# simple-loop-active3.net
KiCad netlist of a schematic drawn in EAGLE
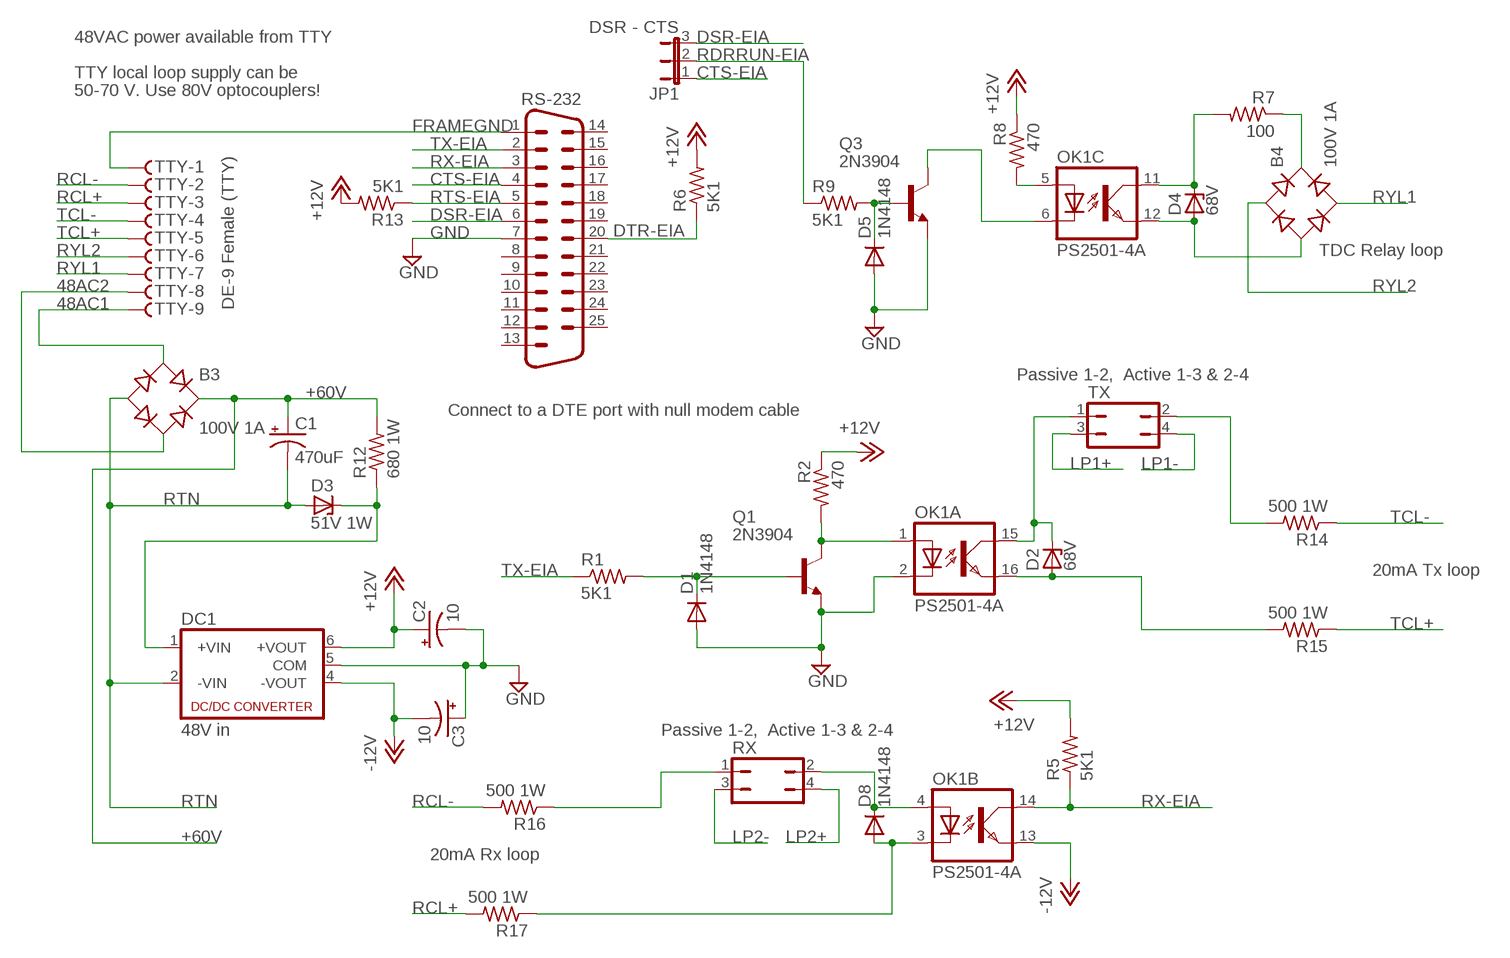
[diagram p0: schematic, sheet 1]
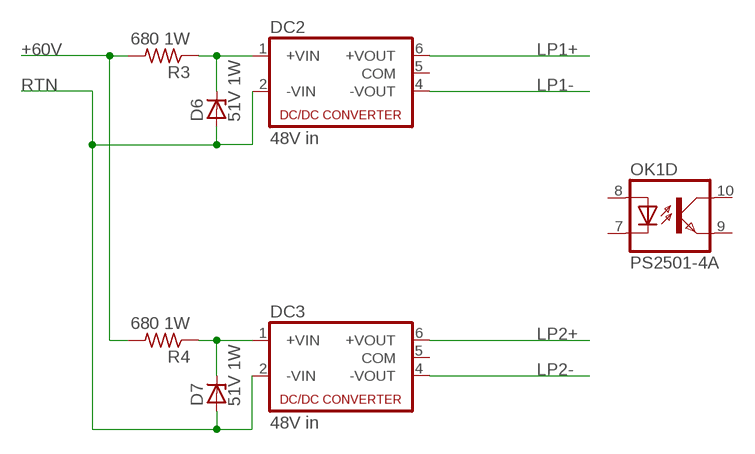
[diagram p1: schematic, sheet 2]

(export (version "E")
  (design (tool "Eeschema 10.0.6"))
  (components
    (comp (ref "D6")
      (value "51V 1W")
      (footprint "eagle-import:DO41Z10")
      (libsource (lib "eagle-import") (part "ZENER-DIODEDO41Z10"))
    )
    (comp (ref "D7")
      (value "51V 1W")
      (footprint "eagle-import:DO41Z10")
      (libsource (lib "eagle-import") (part "ZENER-DIODEDO41Z10"))
    )
    (comp (ref "DC2")
      (value "48V in")
      (footprint "eagle-import:NMA")
      (fields (field (name "MF") "C & D TECHNOLOGIES, INC") (field (name "MPN") "NMA0515SC"))
      (libsource (lib "eagle-import") (part "NMA"))
    )
    (comp (ref "DC3")
      (value "48V in")
      (footprint "eagle-import:NMA")
      (fields (field (name "MF") "C & D TECHNOLOGIES, INC") (field (name "MPN") "NMA0515SC"))
      (libsource (lib "eagle-import") (part "NMA"))
    )
    (comp (ref "OK1")
      (value "PS2501-4A")
      (footprint "eagle-import:DIL16")
      (fields (field (name "MF") "VISHAY/TELEFUNKEN") (field (name "MPN") "ILQ1"))
      (libsource (lib "eagle-import") (part "ILQ1"))
    )
    (comp (ref "R3")
      (value "680 1W")
      (footprint "eagle-import:P0817V")
      (libsource (lib "eagle-import") (part "R-US_0817/7V"))
    )
    (comp (ref "R4")
      (value "680 1W")
      (footprint "eagle-import:P0817V")
      (libsource (lib "eagle-import") (part "R-US_0817/7V"))
    )
    (comp (ref "B3")
      (value "100V 1A")
      (footprint "eagle-import:RB1A")
      (libsource (lib "eagle-import") (part "RB1A"))
    )
    (comp (ref "B4")
      (value "100V 1A")
      (footprint "eagle-import:RB1A")
      (libsource (lib "eagle-import") (part "RB1A"))
    )
    (comp (ref "C1")
      (value "470uF")
      (footprint "eagle-import:E7,5-18")
      (libsource (lib "eagle-import") (part "CPOL-USE7.5-18"))
    )
    (comp (ref "C2")
      (value "10")
      (footprint "eagle-import:B45181A")
      (libsource (lib "eagle-import") (part "CPOL-USB45181A"))
    )
    (comp (ref "C3")
      (value "10")
      (footprint "eagle-import:B45181A")
      (libsource (lib "eagle-import") (part "CPOL-USB45181A"))
    )
    (comp (ref "D1")
      (value "1N4148")
      (footprint "eagle-import:DO35-10")
      (libsource (lib "eagle-import") (part "1N4148DO35-10"))
    )
    (comp (ref "D2")
      (value "68V")
      (footprint "eagle-import:DO41Z10")
      (libsource (lib "eagle-import") (part "ZENER-DIODEDO41Z10"))
    )
    (comp (ref "D3")
      (value "51V 1W")
      (footprint "eagle-import:DO41Z10")
      (libsource (lib "eagle-import") (part "ZENER-DIODEDO41Z10"))
    )
    (comp (ref "D4")
      (value "68V")
      (footprint "eagle-import:DO41Z10")
      (libsource (lib "eagle-import") (part "ZENER-DIODEDO41Z10"))
    )
    (comp (ref "D5")
      (value "1N4148")
      (footprint "eagle-import:DO35-10")
      (libsource (lib "eagle-import") (part "1N4148DO35-10"))
    )
    (comp (ref "D8")
      (value "1N4148")
      (footprint "eagle-import:DO35-10")
      (libsource (lib "eagle-import") (part "1N4148DO35-10"))
    )
    (comp (ref "DC1")
      (value "48V in")
      (footprint "eagle-import:NMA")
      (fields (field (name "MF") "C & D TECHNOLOGIES, INC") (field (name "MPN") "NMA0515SC"))
      (libsource (lib "eagle-import") (part "NMA"))
    )
    (comp (ref "JP1")
      (value "DSR - CTS")
      (footprint "eagle-import:JP2")
      (libsource (lib "eagle-import") (part "JP2E"))
    )
    (comp (ref "Q1")
      (value "2N3904")
      (footprint "eagle-import:TO92")
      (libsource (lib "eagle-import") (part "2N3904"))
    )
    (comp (ref "Q3")
      (value "2N3904")
      (footprint "eagle-import:TO92")
      (libsource (lib "eagle-import") (part "2N3904"))
    )
    (comp (ref "R1")
      (value "5K1")
      (footprint "eagle-import:0207_10")
      (libsource (lib "eagle-import") (part "R-US_0207/10"))
    )
    (comp (ref "R2")
      (value "470")
      (footprint "eagle-import:0207_10")
      (libsource (lib "eagle-import") (part "R-US_0207/10"))
    )
    (comp (ref "R5")
      (value "5K1")
      (footprint "eagle-import:0207_10")
      (libsource (lib "eagle-import") (part "R-US_0207/10"))
    )
    (comp (ref "R6")
      (value "5K1")
      (footprint "eagle-import:0207_10")
      (libsource (lib "eagle-import") (part "R-US_0207/10"))
    )
    (comp (ref "R7")
      (value "100")
      (footprint "eagle-import:0207_10")
      (libsource (lib "eagle-import") (part "R-US_0207/10"))
    )
    (comp (ref "R8")
      (value "470")
      (footprint "eagle-import:0207_10")
      (libsource (lib "eagle-import") (part "R-US_0207/10"))
    )
    (comp (ref "R9")
      (value "5K1")
      (footprint "eagle-import:0207_10")
      (libsource (lib "eagle-import") (part "R-US_0207/10"))
    )
    (comp (ref "R12")
      (value "680 1W")
      (footprint "eagle-import:P0817V")
      (libsource (lib "eagle-import") (part "R-US_0817/7V"))
    )
    (comp (ref "R13")
      (value "5K1")
      (footprint "eagle-import:0207_10")
      (libsource (lib "eagle-import") (part "R-US_0207/10"))
    )
    (comp (ref "R14")
      (value "500 1W")
      (footprint "eagle-import:P0817V")
      (libsource (lib "eagle-import") (part "R-US_0817/7V"))
    )
    (comp (ref "R15")
      (value "500 1W")
      (footprint "eagle-import:P0817V")
      (libsource (lib "eagle-import") (part "R-US_0817/7V"))
    )
    (comp (ref "R16")
      (value "500 1W")
      (footprint "eagle-import:P0817V")
      (libsource (lib "eagle-import") (part "R-US_0817/7V"))
    )
    (comp (ref "R17")
      (value "500 1W")
      (footprint "eagle-import:P0817V")
      (libsource (lib "eagle-import") (part "R-US_0817/7V"))
    )
    (comp (ref "RS-232")
      (value "M25H")
      (footprint "eagle-import:M25H")
      (libsource (lib "eagle-import") (part "M25H"))
    )
    (comp (ref "RX")
      (value "JP2Q")
      (footprint "eagle-import:JP2Q")
      (libsource (lib "eagle-import") (part "JP2Q"))
    )
    (comp (ref "TTY")
      (value "F09HS")
      (footprint "eagle-import:F09H")
      (libsource (lib "eagle-import") (part "F09?SH"))
    )
    (comp (ref "TX")
      (value "JP2Q")
      (footprint "eagle-import:JP2Q")
      (libsource (lib "eagle-import") (part "JP2Q"))
    )
  )
  (nets
    (net (code "1") (name "+12V") (class "Default")
      (node (ref "C2") (pin "+") (pinfunction "+_+") (pintype "passive"))
      (node (ref "DC1") (pin "6") (pinfunction "+VOUT_6") (pintype "passive"))
      (node (ref "R13") (pin "2") (pinfunction "2_2") (pintype "passive"))
      (node (ref "R2") (pin "1") (pinfunction "1_1") (pintype "passive"))
      (node (ref "R5") (pin "2") (pinfunction "2_2") (pintype "passive"))
      (node (ref "R6") (pin "2") (pinfunction "2_2") (pintype "passive"))
      (node (ref "R8") (pin "1") (pinfunction "1_1") (pintype "passive"))
    )
    (net (code "2") (name "+60V") (class "Default")
      (node (ref "B3") (pin "+") (pinfunction "+_+") (pintype "passive"))
      (node (ref "C1") (pin "+") (pinfunction "+_+") (pintype "passive"))
      (node (ref "R12") (pin "2") (pinfunction "2_2") (pintype "passive"))
      (node (ref "R3") (pin "2") (pinfunction "2_2") (pintype "passive"))
      (node (ref "R4") (pin "2") (pinfunction "2_2") (pintype "passive"))
    )
    (net (code "3") (name "-12V") (class "Default")
      (node (ref "C3") (pin "-") (pinfunction "-_-") (pintype "passive"))
      (node (ref "DC1") (pin "4") (pinfunction "-VOUT_4") (pintype "passive"))
      (node (ref "OK1") (pin "13") (pinfunction "EMIT_13") (pintype "passive"))
    )
    (net (code "4") (name "48AC1") (class "Default")
      (node (ref "B3") (pin "AC1") (pinfunction "AC1_AC1") (pintype "passive"))
      (node (ref "TTY") (pin "9") (pinfunction "F_9") (pintype "passive"))
    )
    (net (code "5") (name "48AC2") (class "Default")
      (node (ref "B3") (pin "AC2") (pinfunction "AC2_AC2") (pintype "passive"))
      (node (ref "TTY") (pin "8") (pinfunction "F_8") (pintype "passive"))
    )
    (net (code "6") (name "CTS-EIA") (class "Default")
      (node (ref "JP1") (pin "1") (pinfunction "1_1") (pintype "passive"))
      (node (ref "RS-232") (pin "4") (pinfunction "4_4") (pintype "passive"))
    )
    (net (code "7") (name "DSR-EIA") (class "Default")
      (node (ref "JP1") (pin "3") (pinfunction "3_3") (pintype "passive"))
      (node (ref "RS-232") (pin "6") (pinfunction "6_6") (pintype "passive"))
    )
    (net (code "8") (name "DTR-EIA") (class "Default")
      (node (ref "R6") (pin "1") (pinfunction "1_1") (pintype "passive"))
      (node (ref "RS-232") (pin "20") (pinfunction "20_20") (pintype "passive"))
    )
    (net (code "9") (name "FRAMEGND") (class "Default")
      (node (ref "RS-232") (pin "1") (pinfunction "1_1") (pintype "passive"))
      (node (ref "TTY") (pin "1") (pinfunction "F_1") (pintype "passive"))
    )
    (net (code "10") (name "GND") (class "Default")
      (node (ref "C2") (pin "-") (pinfunction "-_-") (pintype "passive"))
      (node (ref "C3") (pin "+") (pinfunction "+_+") (pintype "passive"))
      (node (ref "D1") (pin "A") (pinfunction "A_A") (pintype "passive"))
      (node (ref "D5") (pin "A") (pinfunction "A_A") (pintype "passive"))
      (node (ref "DC1") (pin "5") (pinfunction "COM_5") (pintype "passive"))
      (node (ref "OK1") (pin "2") (pinfunction "C_2") (pintype "passive"))
      (node (ref "Q1") (pin "3") (pinfunction "E_3") (pintype "passive"))
      (node (ref "Q3") (pin "3") (pinfunction "E_3") (pintype "passive"))
      (node (ref "RS-232") (pin "7") (pinfunction "7_7") (pintype "passive"))
    )
    (net (code "11") (name "LP1+") (class "Default")
      (node (ref "DC2") (pin "6") (pinfunction "+VOUT_6") (pintype "passive"))
      (node (ref "TX") (pin "3") (pinfunction "3_3") (pintype "passive"))
    )
    (net (code "12") (name "LP1-") (class "Default")
      (node (ref "DC2") (pin "4") (pinfunction "-VOUT_4") (pintype "passive"))
      (node (ref "TX") (pin "4") (pinfunction "4_4") (pintype "passive"))
    )
    (net (code "13") (name "LP2+") (class "Default")
      (node (ref "DC3") (pin "6") (pinfunction "+VOUT_6") (pintype "passive"))
      (node (ref "RX") (pin "4") (pinfunction "4_4") (pintype "passive"))
    )
    (net (code "14") (name "LP2-") (class "Default")
      (node (ref "DC3") (pin "4") (pinfunction "-VOUT_4") (pintype "passive"))
      (node (ref "RX") (pin "3") (pinfunction "3_3") (pintype "passive"))
    )
    (net (code "15") (name "Net-(B4-Pad+)") (class "Default")
      (node (ref "B4") (pin "+") (pinfunction "+_+") (pintype "passive"))
      (node (ref "R7") (pin "1") (pinfunction "1_1") (pintype "passive"))
    )
    (net (code "16") (name "Net-(DC1-+VIN)") (class "Default")
      (node (ref "D3") (pin "C") (pinfunction "C_C") (pintype "passive"))
      (node (ref "DC1") (pin "1") (pinfunction "+VIN_1") (pintype "passive"))
      (node (ref "R12") (pin "1") (pinfunction "1_1") (pintype "passive"))
    )
    (net (code "17") (name "Net-(DC2-+VIN)") (class "Default")
      (node (ref "D6") (pin "C") (pinfunction "C_C") (pintype "passive"))
      (node (ref "DC2") (pin "1") (pinfunction "+VIN_1") (pintype "passive"))
      (node (ref "R3") (pin "1") (pinfunction "1_1") (pintype "passive"))
    )
    (net (code "18") (name "Net-(DC3-+VIN)") (class "Default")
      (node (ref "D7") (pin "C") (pinfunction "C_C") (pintype "passive"))
      (node (ref "DC3") (pin "1") (pinfunction "+VIN_1") (pintype "passive"))
      (node (ref "R4") (pin "1") (pinfunction "1_1") (pintype "passive"))
    )
    (net (code "19") (name "Net-(OK1A-A)") (class "Default")
      (node (ref "OK1") (pin "1") (pinfunction "A_1") (pintype "passive"))
      (node (ref "Q1") (pin "1") (pinfunction "C_1") (pintype "passive"))
      (node (ref "R2") (pin "2") (pinfunction "2_2") (pintype "passive"))
    )
    (net (code "20") (name "Net-(OK1A-COL)") (class "Default")
      (node (ref "D2") (pin "C") (pinfunction "C_C") (pintype "passive"))
      (node (ref "OK1") (pin "15") (pinfunction "COL_15") (pintype "passive"))
      (node (ref "TX") (pin "1") (pinfunction "1_1") (pintype "passive"))
    )
    (net (code "21") (name "Net-(OK1A-EMIT)") (class "Default")
      (node (ref "D2") (pin "A") (pinfunction "A_A") (pintype "passive"))
      (node (ref "OK1") (pin "16") (pinfunction "EMIT_16") (pintype "passive"))
      (node (ref "R15") (pin "2") (pinfunction "2_2") (pintype "passive"))
    )
    (net (code "22") (name "Net-(OK1B-A)") (class "Default")
      (node (ref "D8") (pin "C") (pinfunction "C_C") (pintype "passive"))
      (node (ref "OK1") (pin "4") (pinfunction "A_4") (pintype "passive"))
      (node (ref "RX") (pin "2") (pinfunction "2_2") (pintype "passive"))
    )
    (net (code "23") (name "Net-(OK1B-C)") (class "Default")
      (node (ref "D8") (pin "A") (pinfunction "A_A") (pintype "passive"))
      (node (ref "OK1") (pin "3") (pinfunction "C_3") (pintype "passive"))
      (node (ref "R17") (pin "1") (pinfunction "1_1") (pintype "passive"))
    )
    (net (code "24") (name "Net-(OK1C-A)") (class "Default")
      (node (ref "OK1") (pin "5") (pinfunction "A_5") (pintype "passive"))
      (node (ref "R8") (pin "2") (pinfunction "2_2") (pintype "passive"))
    )
    (net (code "25") (name "Net-(OK1C-C)") (class "Default")
      (node (ref "OK1") (pin "6") (pinfunction "C_6") (pintype "passive"))
      (node (ref "Q3") (pin "1") (pinfunction "C_1") (pintype "passive"))
    )
    (net (code "26") (name "Net-(OK1C-COL)") (class "Default")
      (node (ref "D4") (pin "C") (pinfunction "C_C") (pintype "passive"))
      (node (ref "OK1") (pin "11") (pinfunction "COL_11") (pintype "passive"))
      (node (ref "R7") (pin "2") (pinfunction "2_2") (pintype "passive"))
    )
    (net (code "27") (name "Net-(OK1C-EMIT)") (class "Default")
      (node (ref "B4") (pin "-") (pinfunction "-_-") (pintype "passive"))
      (node (ref "D4") (pin "A") (pinfunction "A_A") (pintype "passive"))
      (node (ref "OK1") (pin "12") (pinfunction "EMIT_12") (pintype "passive"))
    )
    (net (code "28") (name "Net-(Q1-B)") (class "Default")
      (node (ref "D1") (pin "C") (pinfunction "C_C") (pintype "passive"))
      (node (ref "Q1") (pin "2") (pinfunction "B_2") (pintype "passive"))
      (node (ref "R1") (pin "2") (pinfunction "2_2") (pintype "passive"))
    )
    (net (code "29") (name "Net-(Q3-B)") (class "Default")
      (node (ref "D5") (pin "C") (pinfunction "C_C") (pintype "passive"))
      (node (ref "Q3") (pin "2") (pinfunction "B_2") (pintype "passive"))
      (node (ref "R9") (pin "2") (pinfunction "2_2") (pintype "passive"))
    )
    (net (code "30") (name "Net-(R14-Pad2)") (class "Default")
      (node (ref "R14") (pin "2") (pinfunction "2_2") (pintype "passive"))
      (node (ref "TX") (pin "2") (pinfunction "2_2") (pintype "passive"))
    )
    (net (code "31") (name "Net-(R16-Pad1)") (class "Default")
      (node (ref "R16") (pin "1") (pinfunction "1_1") (pintype "passive"))
      (node (ref "RX") (pin "1") (pinfunction "1_1") (pintype "passive"))
    )
    (net (code "32") (name "RCL+") (class "Default")
      (node (ref "R17") (pin "2") (pinfunction "2_2") (pintype "passive"))
      (node (ref "TTY") (pin "3") (pinfunction "F_3") (pintype "passive"))
    )
    (net (code "33") (name "RCL-") (class "Default")
      (node (ref "R16") (pin "2") (pinfunction "2_2") (pintype "passive"))
      (node (ref "TTY") (pin "2") (pinfunction "F_2") (pintype "passive"))
    )
    (net (code "34") (name "RDRRUN-EIA") (class "Default")
      (node (ref "JP1") (pin "2") (pinfunction "2_2") (pintype "passive"))
      (node (ref "R9") (pin "1") (pinfunction "1_1") (pintype "passive"))
    )
    (net (code "35") (name "RTN") (class "Default")
      (node (ref "B3") (pin "-") (pinfunction "-_-") (pintype "passive"))
      (node (ref "C1") (pin "-") (pinfunction "-_-") (pintype "passive"))
      (node (ref "D3") (pin "A") (pinfunction "A_A") (pintype "passive"))
      (node (ref "D6") (pin "A") (pinfunction "A_A") (pintype "passive"))
      (node (ref "D7") (pin "A") (pinfunction "A_A") (pintype "passive"))
      (node (ref "DC1") (pin "2") (pinfunction "-VIN_2") (pintype "passive"))
      (node (ref "DC2") (pin "2") (pinfunction "-VIN_2") (pintype "passive"))
      (node (ref "DC3") (pin "2") (pinfunction "-VIN_2") (pintype "passive"))
    )
    (net (code "36") (name "RTS-EIA") (class "Default")
      (node (ref "R13") (pin "1") (pinfunction "1_1") (pintype "passive"))
      (node (ref "RS-232") (pin "5") (pinfunction "5_5") (pintype "passive"))
    )
    (net (code "37") (name "RX-EIA") (class "Default")
      (node (ref "OK1") (pin "14") (pinfunction "COL_14") (pintype "passive"))
      (node (ref "R5") (pin "1") (pinfunction "1_1") (pintype "passive"))
      (node (ref "RS-232") (pin "3") (pinfunction "3_3") (pintype "passive"))
    )
    (net (code "38") (name "RYL1") (class "Default")
      (node (ref "B4") (pin "AC2") (pinfunction "AC2_AC2") (pintype "passive"))
      (node (ref "TTY") (pin "7") (pinfunction "F_7") (pintype "passive"))
    )
    (net (code "39") (name "RYL2") (class "Default")
      (node (ref "B4") (pin "AC1") (pinfunction "AC1_AC1") (pintype "passive"))
      (node (ref "TTY") (pin "6") (pinfunction "F_6") (pintype "passive"))
    )
    (net (code "40") (name "TCL+") (class "Default")
      (node (ref "R15") (pin "1") (pinfunction "1_1") (pintype "passive"))
      (node (ref "TTY") (pin "5") (pinfunction "F_5") (pintype "passive"))
    )
    (net (code "41") (name "TCL-") (class "Default")
      (node (ref "R14") (pin "1") (pinfunction "1_1") (pintype "passive"))
      (node (ref "TTY") (pin "4") (pinfunction "F_4") (pintype "passive"))
    )
    (net (code "42") (name "TX-EIA") (class "Default")
      (node (ref "R1") (pin "1") (pinfunction "1_1") (pintype "passive"))
      (node (ref "RS-232") (pin "2") (pinfunction "2_2") (pintype "passive"))
    )
    (net (code "43") (name "unconnected-(DC2-COM-Pad5)") (class "Default")
      (node (ref "DC2") (pin "5") (pinfunction "COM_5") (pintype "passive"))
    )
    (net (code "44") (name "unconnected-(DC3-COM-Pad5)") (class "Default")
      (node (ref "DC3") (pin "5") (pinfunction "COM_5") (pintype "passive"))
    )
    (net (code "45") (name "unconnected-(OK1D-A-Pad8)") (class "Default")
      (node (ref "OK1") (pin "8") (pinfunction "A_8") (pintype "passive"))
    )
    (net (code "46") (name "unconnected-(OK1D-C-Pad7)") (class "Default")
      (node (ref "OK1") (pin "7") (pinfunction "C_7") (pintype "passive"))
    )
    (net (code "47") (name "unconnected-(OK1D-COL-Pad10)") (class "Default")
      (node (ref "OK1") (pin "10") (pinfunction "COL_10") (pintype "passive"))
    )
    (net (code "48") (name "unconnected-(OK1D-EMIT-Pad9)") (class "Default")
      (node (ref "OK1") (pin "9") (pinfunction "EMIT_9") (pintype "passive"))
    )
    (net (code "49") (name "unconnected-(RS-232-Pad8)") (class "Default")
      (node (ref "RS-232") (pin "8") (pinfunction "8_8") (pintype "passive"))
    )
    (net (code "50") (name "unconnected-(RS-232-Pad9)") (class "Default")
      (node (ref "RS-232") (pin "9") (pinfunction "9_9") (pintype "passive"))
    )
    (net (code "51") (name "unconnected-(RS-232-Pad10)") (class "Default")
      (node (ref "RS-232") (pin "10") (pinfunction "10_10") (pintype "passive"))
    )
    (net (code "52") (name "unconnected-(RS-232-Pad11)") (class "Default")
      (node (ref "RS-232") (pin "11") (pinfunction "11_11") (pintype "passive"))
    )
    (net (code "53") (name "unconnected-(RS-232-Pad12)") (class "Default")
      (node (ref "RS-232") (pin "12") (pinfunction "12_12") (pintype "passive"))
    )
    (net (code "54") (name "unconnected-(RS-232-Pad13)") (class "Default")
      (node (ref "RS-232") (pin "13") (pinfunction "13_13") (pintype "passive"))
    )
    (net (code "55") (name "unconnected-(RS-232-Pad14)") (class "Default")
      (node (ref "RS-232") (pin "14") (pinfunction "14_14") (pintype "passive"))
    )
    (net (code "56") (name "unconnected-(RS-232-Pad15)") (class "Default")
      (node (ref "RS-232") (pin "15") (pinfunction "15_15") (pintype "passive"))
    )
    (net (code "57") (name "unconnected-(RS-232-Pad16)") (class "Default")
      (node (ref "RS-232") (pin "16") (pinfunction "16_16") (pintype "passive"))
    )
    (net (code "58") (name "unconnected-(RS-232-Pad17)") (class "Default")
      (node (ref "RS-232") (pin "17") (pinfunction "17_17") (pintype "passive"))
    )
    (net (code "59") (name "unconnected-(RS-232-Pad18)") (class "Default")
      (node (ref "RS-232") (pin "18") (pinfunction "18_18") (pintype "passive"))
    )
    (net (code "60") (name "unconnected-(RS-232-Pad19)") (class "Default")
      (node (ref "RS-232") (pin "19") (pinfunction "19_19") (pintype "passive"))
    )
    (net (code "61") (name "unconnected-(RS-232-Pad21)") (class "Default")
      (node (ref "RS-232") (pin "21") (pinfunction "21_21") (pintype "passive"))
    )
    (net (code "62") (name "unconnected-(RS-232-Pad22)") (class "Default")
      (node (ref "RS-232") (pin "22") (pinfunction "22_22") (pintype "passive"))
    )
    (net (code "63") (name "unconnected-(RS-232-Pad23)") (class "Default")
      (node (ref "RS-232") (pin "23") (pinfunction "23_23") (pintype "passive"))
    )
    (net (code "64") (name "unconnected-(RS-232-Pad24)") (class "Default")
      (node (ref "RS-232") (pin "24") (pinfunction "24_24") (pintype "passive"))
    )
    (net (code "65") (name "unconnected-(RS-232-Pad25)") (class "Default")
      (node (ref "RS-232") (pin "25") (pinfunction "25_25") (pintype "passive"))
    )
  )
)
